# Top.net
KiCad netlist of a schematic drawn in Altium Designer
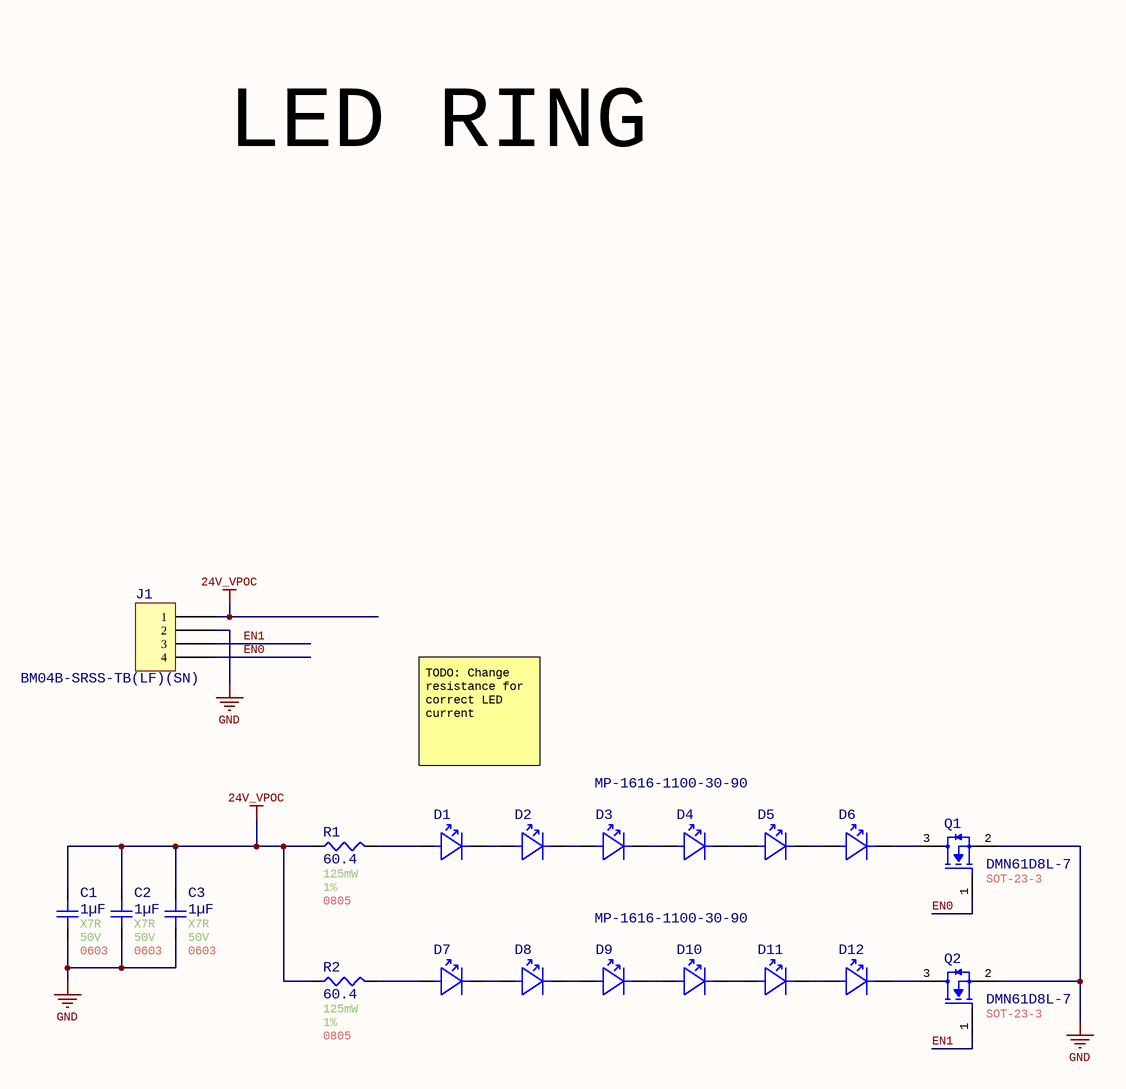
[diagram p0: Top.SchDoc]

(export (version "E")
  (design (tool "Eeschema 10.0.6"))
  (components
    (comp (ref "C1")
      (value "1µF")
      (footprint "Generic 0603 Capacitor")
      (description "Automotive Grade, Mlcc, 0603, X7R, 5")
      (fields
        (field (name "TEMPERATURE COEFFICIENT") "X7R")
        (field (name "VOLTAGE RATING") "50V")
        (field (name "CASE/PACKAGE") "0603")
        (field (name "TOLERANCE") "10%")
        (field (name "Comment") "CGA3E3X7R1H105K080AB")
      )
      (libsource (lib "Raise Robotics") (part "Unpolarized Capacitor"))
    )
    (comp (ref "C2")
      (value "1µF")
      (footprint "Generic 0603 Capacitor")
      (description "Automotive Grade, Mlcc, 0603, X7R, 5")
      (fields
        (field (name "TEMPERATURE COEFFICIENT") "X7R")
        (field (name "VOLTAGE RATING") "50V")
        (field (name "CASE/PACKAGE") "0603")
        (field (name "TOLERANCE") "10%")
        (field (name "Comment") "CGA3E3X7R1H105K080AB")
      )
      (libsource (lib "Raise Robotics") (part "Unpolarized Capacitor"))
    )
    (comp (ref "C3")
      (value "1µF")
      (footprint "Generic 0603 Capacitor")
      (description "Automotive Grade, Mlcc, 0603, X7R, 5")
      (fields
        (field (name "TEMPERATURE COEFFICIENT") "X7R")
        (field (name "VOLTAGE RATING") "50V")
        (field (name "CASE/PACKAGE") "0603")
        (field (name "TOLERANCE") "10%")
        (field (name "Comment") "CGA3E3X7R1H105K080AB")
      )
      (libsource (lib "Raise Robotics") (part "Unpolarized Capacitor"))
    )
    (comp (ref "D1")
      (value "MP-1616-1100-30-90")
      (footprint "1616_1.6x1.6x0.9_LED")
      (description "Single Color LED, Warm White, 1.6mm")
      (libsource (lib "Raise Robotics") (part "LED"))
    )
    (comp (ref "D2")
      (value "MP-1616-1100-30-90")
      (footprint "1616_1.6x1.6x0.9_LED")
      (description "Single Color LED, Warm White, 1.6mm")
      (libsource (lib "Raise Robotics") (part "LED"))
    )
    (comp (ref "D3")
      (value "MP-1616-1100-30-90")
      (footprint "1616_1.6x1.6x0.9_LED")
      (description "Single Color LED, Warm White, 1.6mm")
      (libsource (lib "Raise Robotics") (part "LED"))
    )
    (comp (ref "D4")
      (value "MP-1616-1100-30-90")
      (footprint "1616_1.6x1.6x0.9_LED")
      (description "Single Color LED, Warm White, 1.6mm")
      (libsource (lib "Raise Robotics") (part "LED"))
    )
    (comp (ref "D5")
      (value "MP-1616-1100-30-90")
      (footprint "1616_1.6x1.6x0.9_LED")
      (description "Single Color LED, Warm White, 1.6mm")
      (libsource (lib "Raise Robotics") (part "LED"))
    )
    (comp (ref "D6")
      (value "MP-1616-1100-30-90")
      (footprint "1616_1.6x1.6x0.9_LED")
      (description "Single Color LED, Warm White, 1.6mm")
      (libsource (lib "Raise Robotics") (part "LED"))
    )
    (comp (ref "D7")
      (value "MP-1616-1100-30-90")
      (footprint "1616_1.6x1.6x0.9_LED")
      (description "Single Color LED, Warm White, 1.6mm")
      (libsource (lib "Raise Robotics") (part "LED"))
    )
    (comp (ref "D8")
      (value "MP-1616-1100-30-90")
      (footprint "1616_1.6x1.6x0.9_LED")
      (description "Single Color LED, Warm White, 1.6mm")
      (libsource (lib "Raise Robotics") (part "LED"))
    )
    (comp (ref "D9")
      (value "MP-1616-1100-30-90")
      (footprint "1616_1.6x1.6x0.9_LED")
      (description "Single Color LED, Warm White, 1.6mm")
      (libsource (lib "Raise Robotics") (part "LED"))
    )
    (comp (ref "D10")
      (value "MP-1616-1100-30-90")
      (footprint "1616_1.6x1.6x0.9_LED")
      (description "Single Color LED, Warm White, 1.6mm")
      (libsource (lib "Raise Robotics") (part "LED"))
    )
    (comp (ref "D11")
      (value "MP-1616-1100-30-90")
      (footprint "1616_1.6x1.6x0.9_LED")
      (description "Single Color LED, Warm White, 1.6mm")
      (libsource (lib "Raise Robotics") (part "LED"))
    )
    (comp (ref "D12")
      (value "MP-1616-1100-30-90")
      (footprint "1616_1.6x1.6x0.9_LED")
      (description "Single Color LED, Warm White, 1.6mm")
      (libsource (lib "Raise Robotics") (part "LED"))
    )
    (comp (ref "J1")
      (value "BM04B-SRSS-TB(LF)(SN)")
      (footprint "JST BM04B-SRSS-TB")
      (description "CONN HEADER SMD 4POS 1MM")
      (fields (field (name "MANUFACTURER") "JST Sales America Inc."))
      (libsource (lib "Celestial Altium Library - altium_library") (part "4 Pin"))
    )
    (comp (ref "Q1")
      (value "DMN61D8L-7")
      (footprint "Diodes SOT23")
      (description "DMN61D8L Series 60 V 470 mA 1.8 Ohm Surface Mount N-Channel Mosfet - SOT-23-3")
      (fields (field (name "CASE/PACKAGE") "SOT-23-3"))
      (libsource (lib "Raise Robotics") (part "n-FET 3 pin SOT"))
    )
    (comp (ref "Q2")
      (value "DMN61D8L-7")
      (footprint "Diodes SOT23")
      (description "DMN61D8L Series 60 V 470 mA 1.8 Ohm Surface Mount N-Channel Mosfet - SOT-23-3")
      (fields (field (name "CASE/PACKAGE") "SOT-23-3"))
      (libsource (lib "Raise Robotics") (part "n-FET 3 pin SOT"))
    )
    (comp (ref "R1")
      (value "60.4")
      (footprint "0805 Resistor")
      (description "Res 60.4 Ohm 1% 1/8W 0805")
      (fields
        (field (name "POWER") "125mW")
        (field (name "TOLERANCE") "1%")
        (field (name "CASE/PACKAGE") "0805")
        (field (name "MANUFACTURER PART NUMBER") "TFA0805R60R4F-T5")
      )
      (libsource (lib "Raise Robotics") (part "Resistor"))
    )
    (comp (ref "R2")
      (value "60.4")
      (footprint "0805 Resistor")
      (description "Res 60.4 Ohm 1% 1/8W 0805")
      (fields
        (field (name "POWER") "125mW")
        (field (name "TOLERANCE") "1%")
        (field (name "CASE/PACKAGE") "0805")
        (field (name "MANUFACTURER PART NUMBER") "TFA0805R60R4F-T5")
      )
      (libsource (lib "Raise Robotics") (part "Resistor"))
    )
  )
  (nets
    (net (code "1") (name "/EN0") (class "Default")
      (node (ref "J1") (pin "4") (pinfunction "4_4") (pintype "passive"))
      (node (ref "Q1") (pin "1") (pinfunction "GATE_1") (pintype "passive"))
    )
    (net (code "2") (name "/EN1") (class "Default")
      (node (ref "J1") (pin "3") (pinfunction "3_3") (pintype "passive"))
      (node (ref "Q2") (pin "1") (pinfunction "GATE_1") (pintype "passive"))
    )
    (net (code "3") (name "24V_VPOC") (class "Default")
      (node (ref "C1") (pin "2") (pinfunction "2_2") (pintype "passive"))
      (node (ref "C2") (pin "2") (pinfunction "2_2") (pintype "passive"))
      (node (ref "C3") (pin "2") (pinfunction "2_2") (pintype "passive"))
      (node (ref "J1") (pin "1") (pinfunction "1_1") (pintype "passive"))
      (node (ref "R1") (pin "1") (pinfunction "1_1") (pintype "passive"))
      (node (ref "R2") (pin "1") (pinfunction "1_1") (pintype "passive"))
    )
    (net (code "4") (name "GND") (class "Default")
      (node (ref "C1") (pin "1") (pinfunction "1_1") (pintype "passive"))
      (node (ref "C2") (pin "1") (pinfunction "1_1") (pintype "passive"))
      (node (ref "C3") (pin "1") (pinfunction "1_1") (pintype "passive"))
      (node (ref "J1") (pin "2") (pinfunction "2_2") (pintype "passive"))
      (node (ref "Q1") (pin "2") (pinfunction "SOURCE_2") (pintype "passive"))
      (node (ref "Q2") (pin "2") (pinfunction "SOURCE_2") (pintype "passive"))
    )
    (net (code "5") (name "Net-(D1-A)") (class "Default")
      (node (ref "D1") (pin "2") (pinfunction "A_2") (pintype "passive"))
      (node (ref "R1") (pin "2") (pinfunction "2_2") (pintype "passive"))
    )
    (net (code "6") (name "Net-(D1-C)") (class "Default")
      (node (ref "D1") (pin "1") (pinfunction "C_1") (pintype "passive"))
      (node (ref "D2") (pin "2") (pinfunction "A_2") (pintype "passive"))
    )
    (net (code "7") (name "Net-(D2-C)") (class "Default")
      (node (ref "D2") (pin "1") (pinfunction "C_1") (pintype "passive"))
      (node (ref "D3") (pin "2") (pinfunction "A_2") (pintype "passive"))
    )
    (net (code "8") (name "Net-(D3-C)") (class "Default")
      (node (ref "D3") (pin "1") (pinfunction "C_1") (pintype "passive"))
      (node (ref "D4") (pin "2") (pinfunction "A_2") (pintype "passive"))
    )
    (net (code "9") (name "Net-(D4-C)") (class "Default")
      (node (ref "D4") (pin "1") (pinfunction "C_1") (pintype "passive"))
      (node (ref "D5") (pin "2") (pinfunction "A_2") (pintype "passive"))
    )
    (net (code "10") (name "Net-(D5-C)") (class "Default")
      (node (ref "D5") (pin "1") (pinfunction "C_1") (pintype "passive"))
      (node (ref "D6") (pin "2") (pinfunction "A_2") (pintype "passive"))
    )
    (net (code "11") (name "Net-(D6-C)") (class "Default")
      (node (ref "D6") (pin "1") (pinfunction "C_1") (pintype "passive"))
      (node (ref "Q1") (pin "3") (pinfunction "DRAIN_3") (pintype "passive"))
    )
    (net (code "12") (name "Net-(D7-A)") (class "Default")
      (node (ref "D7") (pin "2") (pinfunction "A_2") (pintype "passive"))
      (node (ref "R2") (pin "2") (pinfunction "2_2") (pintype "passive"))
    )
    (net (code "13") (name "Net-(D7-C)") (class "Default")
      (node (ref "D7") (pin "1") (pinfunction "C_1") (pintype "passive"))
      (node (ref "D8") (pin "2") (pinfunction "A_2") (pintype "passive"))
    )
    (net (code "14") (name "Net-(D8-C)") (class "Default")
      (node (ref "D8") (pin "1") (pinfunction "C_1") (pintype "passive"))
      (node (ref "D9") (pin "2") (pinfunction "A_2") (pintype "passive"))
    )
    (net (code "15") (name "Net-(D10-A)") (class "Default")
      (node (ref "D10") (pin "2") (pinfunction "A_2") (pintype "passive"))
      (node (ref "D9") (pin "1") (pinfunction "C_1") (pintype "passive"))
    )
    (net (code "16") (name "Net-(D10-C)") (class "Default")
      (node (ref "D10") (pin "1") (pinfunction "C_1") (pintype "passive"))
      (node (ref "D11") (pin "2") (pinfunction "A_2") (pintype "passive"))
    )
    (net (code "17") (name "Net-(D11-C)") (class "Default")
      (node (ref "D11") (pin "1") (pinfunction "C_1") (pintype "passive"))
      (node (ref "D12") (pin "2") (pinfunction "A_2") (pintype "passive"))
    )
    (net (code "18") (name "Net-(D12-C)") (class "Default")
      (node (ref "D12") (pin "1") (pinfunction "C_1") (pintype "passive"))
      (node (ref "Q2") (pin "3") (pinfunction "DRAIN_3") (pintype "passive"))
    )
  )
)
